# edison_board.net
KiCad netlist of a schematic drawn in EAGLE
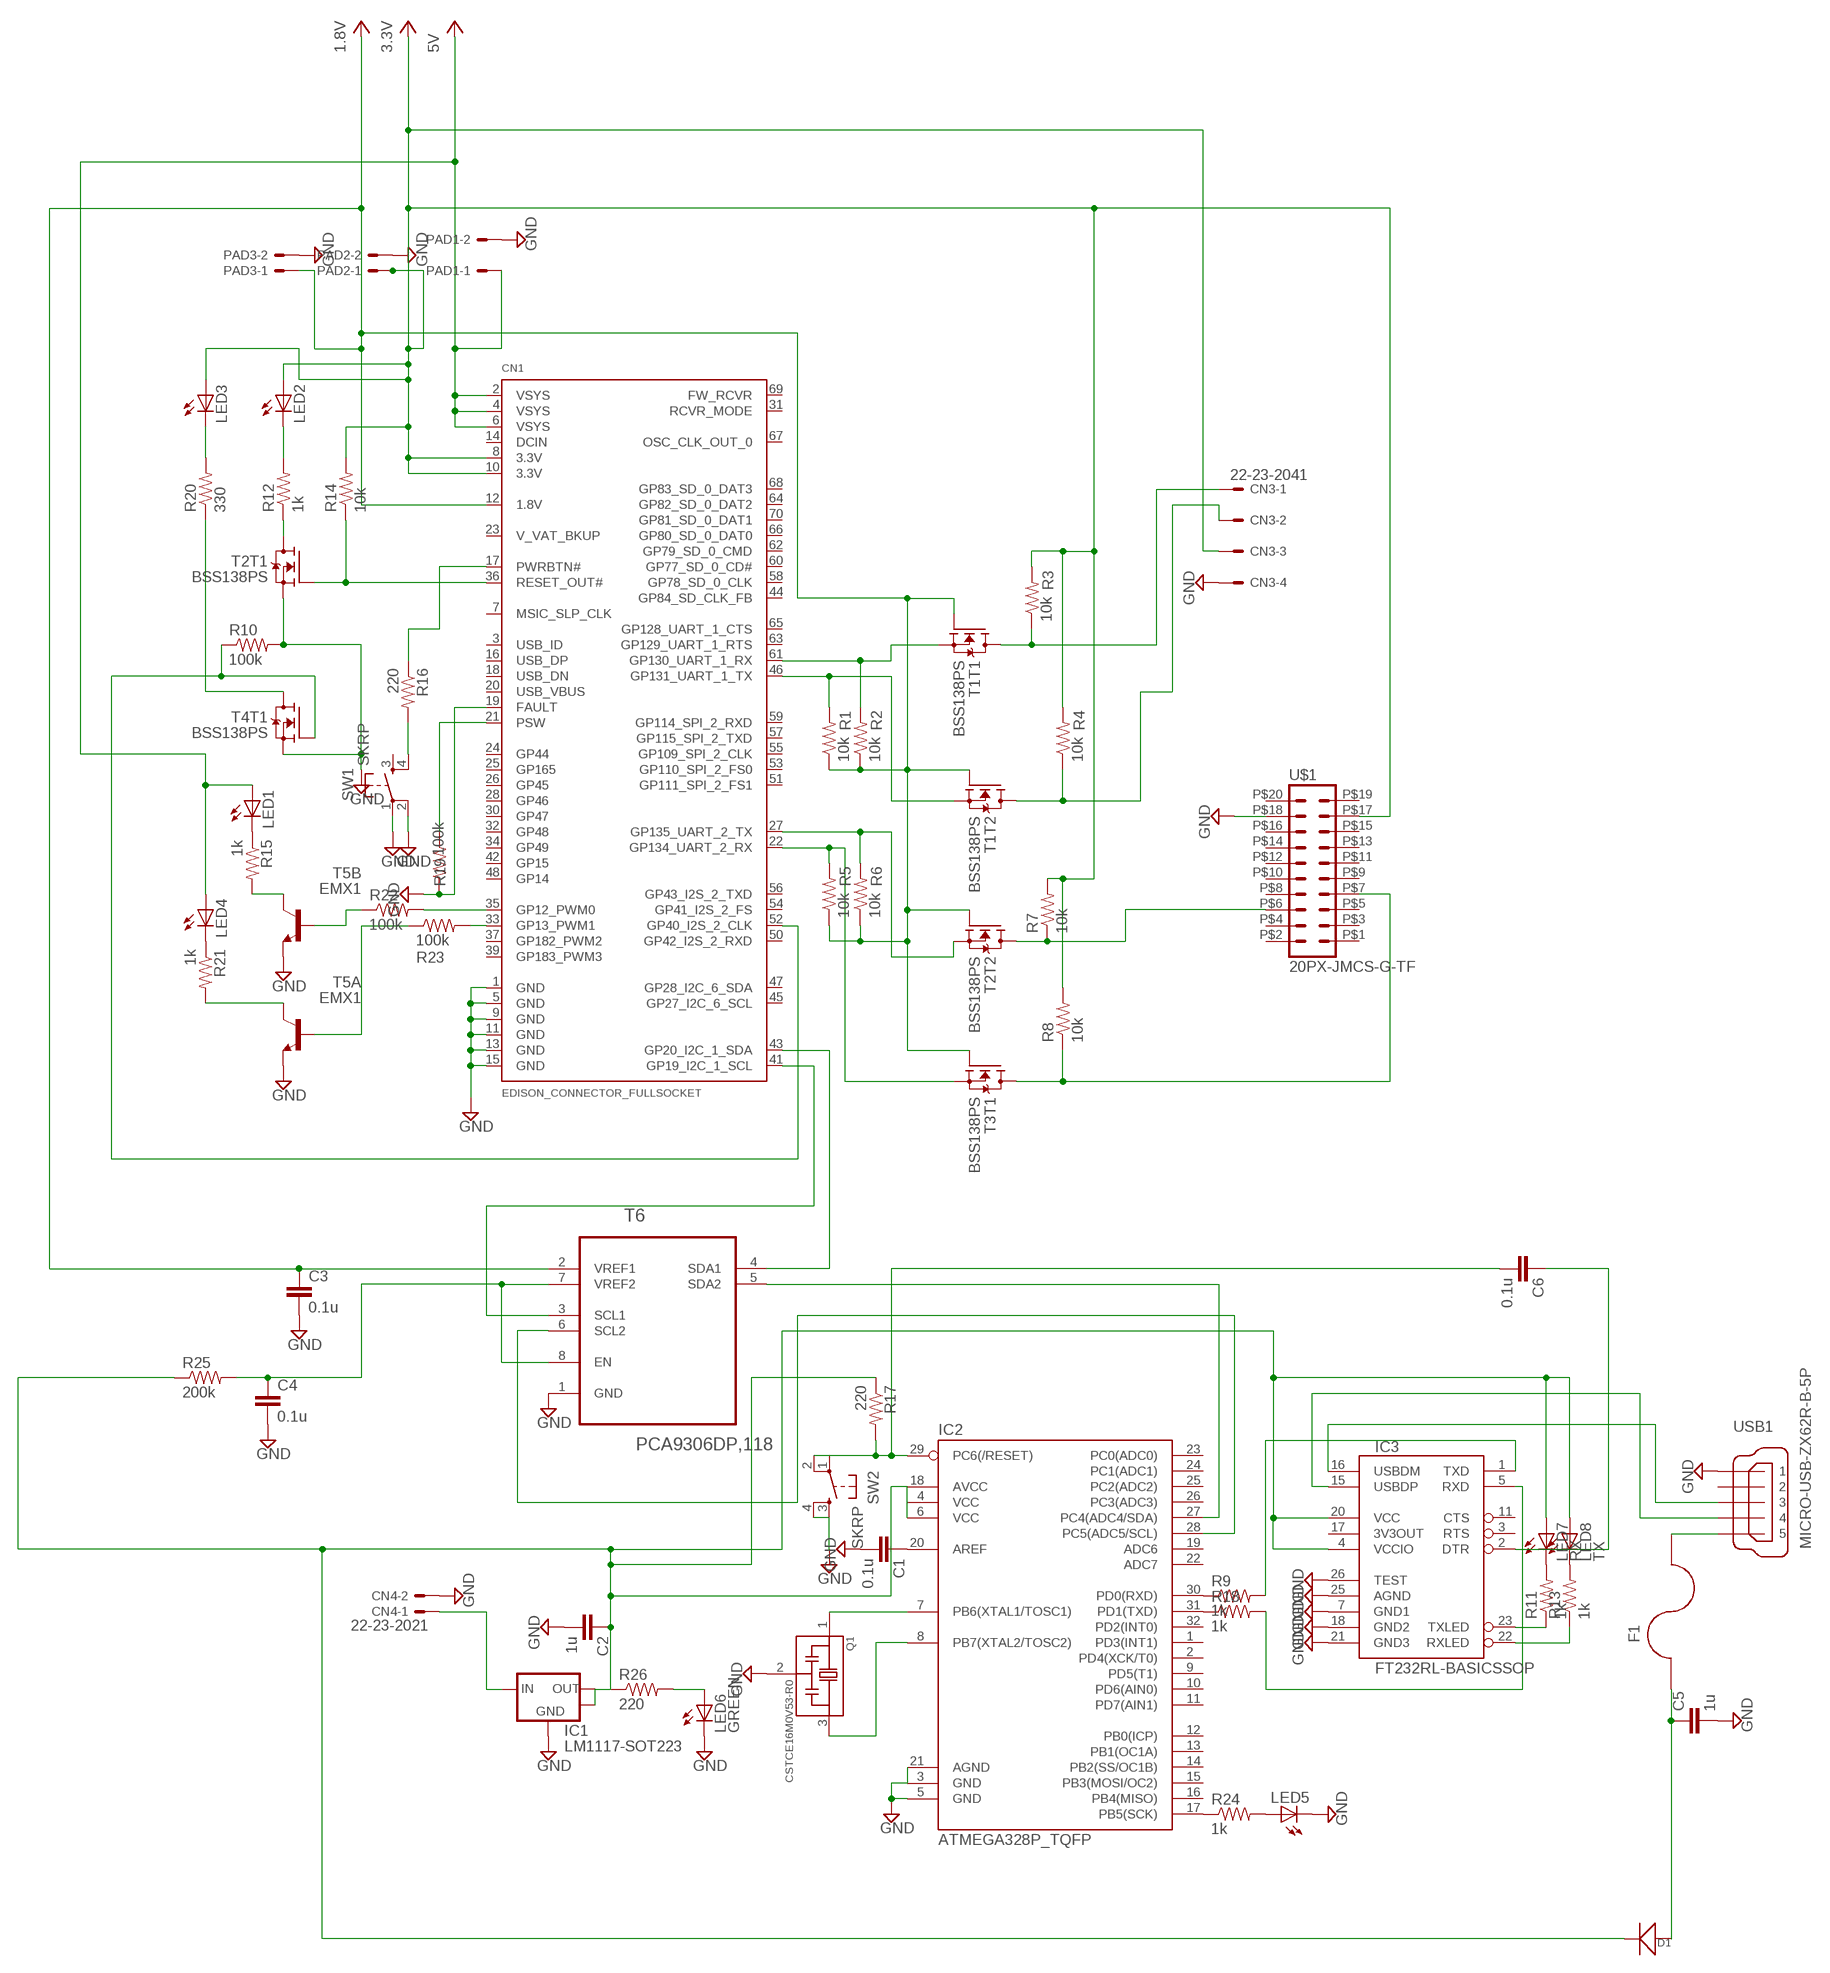
[diagram p0: schematic, sheet 1]

(export (version "E")
  (design (tool "Eeschema 10.0.6"))
  (components
    (comp (ref "C1")
      (value "0.1u")
      (footprint "eagle-import:C0603")
      (libsource (lib "eagle-import") (part "C-EUC0603"))
    )
    (comp (ref "C2")
      (value "1u")
      (footprint "eagle-import:C0603")
      (libsource (lib "eagle-import") (part "C-EUC0603"))
    )
    (comp (ref "C3")
      (value "0.1u")
      (footprint "eagle-import:C0603")
      (libsource (lib "eagle-import") (part "C-EUC0603"))
    )
    (comp (ref "C4")
      (value "0.1u")
      (footprint "eagle-import:C0603")
      (libsource (lib "eagle-import") (part "C-EUC0603"))
    )
    (comp (ref "C5")
      (value "1u")
      (footprint "eagle-import:C0603")
      (libsource (lib "eagle-import") (part "C-EUC0603"))
    )
    (comp (ref "C6")
      (value "0.1u")
      (footprint "eagle-import:C0603")
      (libsource (lib "eagle-import") (part "C-EUC0603"))
    )
    (comp (ref "CN1")
      (value "EDISON_CONNECTOR_FULLSOCKET")
      (footprint "eagle-import:DF40-XC-(X.X)-70DS-0.4V(51)")
      (libsource (lib "eagle-import") (part "EDISON_CONNECTOR_FULLSOCKET"))
    )
    (comp (ref "CN3")
      (value "22-23-2041")
      (footprint "eagle-import:22-23-2041")
      (fields (field (name "MF") "MOLEX"))
      (libsource (lib "eagle-import") (part "22-23-2041"))
    )
    (comp (ref "CN4")
      (value "22-23-2021")
      (footprint "eagle-import:22-23-2021")
      (fields (field (name "MF") "MOLEX"))
      (libsource (lib "eagle-import") (part "22-23-2021"))
    )
    (comp (ref "D1")
      (value "D'DO-220AA'")
      (footprint "eagle-import:DO-220AA")
      (libsource (lib "eagle-import") (part "D'DO-220AA'"))
    )
    (comp (ref "F1")
      (value "MF-MSMF075/24")
      (footprint "eagle-import:1812")
      (fields (field (name "MANUFACTURER") "Bourns Inc.") (field (name "PART_NUMBER") "MF-MSMF075/24-2"))
      (libsource (lib "eagle-import") (part "MF-MSMF?075/24"))
    )
    (comp (ref "IC1")
      (value "LM1117-SOT223")
      (footprint "eagle-import:SOT-223-3")
      (libsource (lib "eagle-import") (part "LM1117-SOT223"))
    )
    (comp (ref "IC2")
      (value "ATMEGA328P_TQFP")
      (footprint "eagle-import:TQFP32-08")
      (libsource (lib "eagle-import") (part "ATMEGA328P_TQFP"))
    )
    (comp (ref "IC3")
      (value "FT232RL-BASICSSOP")
      (footprint "eagle-import:SSOP28DB")
      (libsource (lib "eagle-import") (part "FT232RL-BASICSSOP"))
    )
    (comp (ref "LED1")
      (value "LEDCHIPLED_1206")
      (footprint "eagle-import:CHIPLED_1206")
      (libsource (lib "eagle-import") (part "LEDCHIPLED_1206"))
    )
    (comp (ref "LED2")
      (value "LEDCHIPLED_1206")
      (footprint "eagle-import:CHIPLED_1206")
      (libsource (lib "eagle-import") (part "LEDCHIPLED_1206"))
    )
    (comp (ref "LED3")
      (value "LEDCHIPLED_1206")
      (footprint "eagle-import:CHIPLED_1206")
      (libsource (lib "eagle-import") (part "LEDCHIPLED_1206"))
    )
    (comp (ref "LED4")
      (value "LEDCHIPLED_1206")
      (footprint "eagle-import:CHIPLED_1206")
      (libsource (lib "eagle-import") (part "LEDCHIPLED_1206"))
    )
    (comp (ref "LED5")
      (value "LEDCHIPLED_1206")
      (footprint "eagle-import:CHIPLED_1206")
      (libsource (lib "eagle-import") (part "LEDCHIPLED_1206"))
    )
    (comp (ref "LED6")
      (value "GREEN")
      (footprint "eagle-import:CHIPLED_1206")
      (libsource (lib "eagle-import") (part "LEDCHIPLED_1206"))
    )
    (comp (ref "LED7")
      (value "RX")
      (footprint "eagle-import:CHIPLED_1206")
      (libsource (lib "eagle-import") (part "LEDCHIPLED_1206"))
    )
    (comp (ref "LED8")
      (value "TX")
      (footprint "eagle-import:CHIPLED_1206")
      (libsource (lib "eagle-import") (part "LEDCHIPLED_1206"))
    )
    (comp (ref "PAD1")
      (value "87758-0216")
      (footprint "eagle-import:87758-0216")
      (libsource (lib "eagle-import") (part "87758-0216"))
    )
    (comp (ref "PAD2")
      (value "87758-0216")
      (footprint "eagle-import:87758-0216")
      (libsource (lib "eagle-import") (part "87758-0216"))
    )
    (comp (ref "PAD3")
      (value "87758-0216")
      (footprint "eagle-import:87758-0216")
      (libsource (lib "eagle-import") (part "87758-0216"))
    )
    (comp (ref "Q1")
      (value "CSTCE16M0V53-R0")
      (footprint "eagle-import:OSC_CSTCE16M0V53-R0")
      (fields (field (name "MF") "Murata"))
      (libsource (lib "eagle-import") (part "CSTCE16M0V53-R0"))
    )
    (comp (ref "R1")
      (value "10k")
      (footprint "eagle-import:R0603")
      (libsource (lib "eagle-import") (part "R-US_R0603"))
    )
    (comp (ref "R2")
      (value "10k")
      (footprint "eagle-import:R0603")
      (libsource (lib "eagle-import") (part "R-US_R0603"))
    )
    (comp (ref "R3")
      (value "10k")
      (footprint "eagle-import:R0603")
      (libsource (lib "eagle-import") (part "R-US_R0603"))
    )
    (comp (ref "R4")
      (value "10k")
      (footprint "eagle-import:R0603")
      (libsource (lib "eagle-import") (part "R-US_R0603"))
    )
    (comp (ref "R5")
      (value "10k")
      (footprint "eagle-import:R0603")
      (libsource (lib "eagle-import") (part "R-US_R0603"))
    )
    (comp (ref "R6")
      (value "10k")
      (footprint "eagle-import:R0603")
      (libsource (lib "eagle-import") (part "R-US_R0603"))
    )
    (comp (ref "R7")
      (value "10k")
      (footprint "eagle-import:R0603")
      (libsource (lib "eagle-import") (part "R-US_R0603"))
    )
    (comp (ref "R8")
      (value "10k")
      (footprint "eagle-import:R0603")
      (libsource (lib "eagle-import") (part "R-US_R0603"))
    )
    (comp (ref "R9")
      (value "1k")
      (footprint "eagle-import:R0603")
      (libsource (lib "eagle-import") (part "R-US_R0603"))
    )
    (comp (ref "R10")
      (value "100k")
      (footprint "eagle-import:R0603")
      (libsource (lib "eagle-import") (part "R-US_R0603"))
    )
    (comp (ref "R11")
      (value "1k")
      (footprint "eagle-import:R0603")
      (libsource (lib "eagle-import") (part "R-US_R0603"))
    )
    (comp (ref "R12")
      (value "1k")
      (footprint "eagle-import:R0603")
      (libsource (lib "eagle-import") (part "R-US_R0603"))
    )
    (comp (ref "R13")
      (value "1k")
      (footprint "eagle-import:R0603")
      (libsource (lib "eagle-import") (part "R-US_R0603"))
    )
    (comp (ref "R14")
      (value "10k")
      (footprint "eagle-import:R0603")
      (libsource (lib "eagle-import") (part "R-US_R0603"))
    )
    (comp (ref "R15")
      (value "1k")
      (footprint "eagle-import:R0603")
      (libsource (lib "eagle-import") (part "R-US_R0603"))
    )
    (comp (ref "R16")
      (value "220")
      (footprint "eagle-import:R0603")
      (libsource (lib "eagle-import") (part "R-US_R0603"))
    )
    (comp (ref "R17")
      (value "220")
      (footprint "eagle-import:R0603")
      (libsource (lib "eagle-import") (part "R-US_R0603"))
    )
    (comp (ref "R18")
      (value "1k")
      (footprint "eagle-import:R0603")
      (libsource (lib "eagle-import") (part "R-US_R0603"))
    )
    (comp (ref "R19")
      (value "100k")
      (footprint "eagle-import:R0603")
      (libsource (lib "eagle-import") (part "R-US_R0603"))
    )
    (comp (ref "R20")
      (value "330")
      (footprint "eagle-import:R0603")
      (libsource (lib "eagle-import") (part "R-US_R0603"))
    )
    (comp (ref "R21")
      (value "1k")
      (footprint "eagle-import:R0603")
      (libsource (lib "eagle-import") (part "R-US_R0603"))
    )
    (comp (ref "R22")
      (value "100k")
      (footprint "eagle-import:R0603")
      (libsource (lib "eagle-import") (part "R-US_R0603"))
    )
    (comp (ref "R23")
      (value "100k")
      (footprint "eagle-import:R0603")
      (libsource (lib "eagle-import") (part "R-US_R0603"))
    )
    (comp (ref "R24")
      (value "1k")
      (footprint "eagle-import:R0603")
      (libsource (lib "eagle-import") (part "R-US_R0603"))
    )
    (comp (ref "R25")
      (value "200k")
      (footprint "eagle-import:R0603")
      (libsource (lib "eagle-import") (part "R-US_R0603"))
    )
    (comp (ref "R26")
      (value "220")
      (footprint "eagle-import:R0603")
      (libsource (lib "eagle-import") (part "R-US_R0603"))
    )
    (comp (ref "SW1")
      (value "SKRP")
      (footprint "eagle-import:SKRP")
      (libsource (lib "eagle-import") (part "SKRP"))
    )
    (comp (ref "SW2")
      (value "SKRP")
      (footprint "eagle-import:SKRP")
      (libsource (lib "eagle-import") (part "SKRP"))
    )
    (comp (ref "T1")
      (value "BSS138PS")
      (footprint "eagle-import:SOT363")
      (libsource (lib "eagle-import") (part "BSS138PS"))
    )
    (comp (ref "T2")
      (value "BSS138PS")
      (footprint "eagle-import:SOT363")
      (libsource (lib "eagle-import") (part "BSS138PS"))
    )
    (comp (ref "T3")
      (value "BSS138PS")
      (footprint "eagle-import:SOT363")
      (libsource (lib "eagle-import") (part "BSS138PS"))
    )
    (comp (ref "T4")
      (value "BSS138PS")
      (footprint "eagle-import:SOT363")
      (libsource (lib "eagle-import") (part "BSS138PS"))
    )
    (comp (ref "T5")
      (value "EMX1")
      (footprint "eagle-import:EMT6")
      (fields (field (name "MPN") "EMX1T2R"))
      (libsource (lib "eagle-import") (part "EMX1"))
    )
    (comp (ref "T6")
      (value "PCA9306DP,118")
      (footprint "eagle-import:SOP65P490X110-8N")
      (libsource (lib "eagle-import") (part "PCA9306DP,118"))
    )
    (comp (ref "U$1")
      (value "20PX-JMCS-G-TF")
      (footprint "eagle-import:20PX-JMCS-G-TF")
      (libsource (lib "eagle-import") (part "20PX-JMCS-G-TF"))
    )
    (comp (ref "USB1")
      (value "MICRO-USB-ZX62R-B-5P")
      (footprint "eagle-import:ZX62R-B-5P")
      (libsource (lib "eagle-import") (part "MICRO-USB-ZX62R-B-5P"))
    )
  )
  (nets
    (net (code "1") (name "1.8V") (class "Default")
      (node (ref "C3") (pin "1") (pinfunction "1_1") (pintype "passive"))
      (node (ref "CN1") (pin "12") (pinfunction "1.8V_12") (pintype "bidirectional"))
      (node (ref "CN1") (pin "27") (pinfunction "GP135_UART_2_TX_27") (pintype "bidirectional"))
      (node (ref "PAD3") (pin "1") (pinfunction "S_1") (pintype "passive"))
      (node (ref "R1") (pin "1") (pinfunction "1_1") (pintype "passive"))
      (node (ref "R2") (pin "1") (pinfunction "1_1") (pintype "passive"))
      (node (ref "R5") (pin "1") (pinfunction "1_1") (pintype "passive"))
      (node (ref "R6") (pin "1") (pinfunction "1_1") (pintype "passive"))
      (node (ref "R6") (pin "2") (pinfunction "2_2") (pintype "passive"))
      (node (ref "T1") (pin "2") (pinfunction "G_2") (pintype "passive"))
      (node (ref "T1") (pin "5") (pinfunction "G_5") (pintype "passive"))
      (node (ref "T2") (pin "4") (pinfunction "S_4") (pintype "passive"))
      (node (ref "T2") (pin "5") (pinfunction "G_5") (pintype "passive"))
      (node (ref "T3") (pin "2") (pinfunction "G_2") (pintype "passive"))
      (node (ref "T6") (pin "2") (pinfunction "VREF1_2") (pintype "power_in"))
    )
    (net (code "2") (name "3.3V") (class "Default")
      (node (ref "CN1") (pin "10") (pinfunction "3.3V_10") (pintype "bidirectional"))
      (node (ref "CN1") (pin "8") (pinfunction "3.3V_8") (pintype "bidirectional"))
      (node (ref "CN3") (pin "3") (pinfunction "S_3") (pintype "passive"))
      (node (ref "LED2") (pin "A") (pinfunction "A_A") (pintype "passive"))
      (node (ref "LED3") (pin "A") (pinfunction "A_A") (pintype "passive"))
      (node (ref "PAD2") (pin "1") (pinfunction "S_1") (pintype "passive"))
      (node (ref "R14") (pin "2") (pinfunction "2_2") (pintype "passive"))
      (node (ref "R3") (pin "2") (pinfunction "2_2") (pintype "passive"))
      (node (ref "R4") (pin "2") (pinfunction "2_2") (pintype "passive"))
      (node (ref "R7") (pin "2") (pinfunction "2_2") (pintype "passive"))
      (node (ref "R8") (pin "2") (pinfunction "2_2") (pintype "passive"))
      (node (ref "U$1") (pin "P$17") (pinfunction "17_P$17") (pintype "passive"))
    )
    (net (code "3") (name "5V") (class "Default")
      (node (ref "CN1") (pin "2") (pinfunction "VSYS_2") (pintype "bidirectional"))
      (node (ref "CN1") (pin "4") (pinfunction "VSYS_4") (pintype "bidirectional"))
      (node (ref "CN1") (pin "6") (pinfunction "VSYS_6") (pintype "bidirectional"))
      (node (ref "LED1") (pin "A") (pinfunction "A_A") (pintype "passive"))
      (node (ref "LED4") (pin "A") (pinfunction "A_A") (pintype "passive"))
      (node (ref "PAD1") (pin "1") (pinfunction "S_1") (pintype "passive"))
    )
    (net (code "4") (name "GND") (class "Default")
      (node (ref "C1") (pin "2") (pinfunction "2_2") (pintype "passive"))
      (node (ref "C2") (pin "2") (pinfunction "2_2") (pintype "passive"))
      (node (ref "C3") (pin "2") (pinfunction "2_2") (pintype "passive"))
      (node (ref "C4") (pin "2") (pinfunction "2_2") (pintype "passive"))
      (node (ref "C5") (pin "2") (pinfunction "2_2") (pintype "passive"))
      (node (ref "CN1") (pin "1") (pinfunction "GND_1") (pintype "bidirectional"))
      (node (ref "CN1") (pin "11") (pinfunction "GND_11") (pintype "bidirectional"))
      (node (ref "CN1") (pin "13") (pinfunction "GND_13") (pintype "bidirectional"))
      (node (ref "CN1") (pin "15") (pinfunction "GND_15") (pintype "bidirectional"))
      (node (ref "CN1") (pin "19") (pinfunction "FAULT_19") (pintype "bidirectional"))
      (node (ref "CN1") (pin "5") (pinfunction "GND_5") (pintype "bidirectional"))
      (node (ref "CN1") (pin "9") (pinfunction "GND_9") (pintype "bidirectional"))
      (node (ref "CN3") (pin "4") (pinfunction "S_4") (pintype "passive"))
      (node (ref "CN4") (pin "2") (pinfunction "S_2") (pintype "passive"))
      (node (ref "IC1") (pin "1") (pinfunction "GND_1") (pintype "bidirectional"))
      (node (ref "IC2") (pin "21") (pinfunction "AGND_21") (pintype "bidirectional"))
      (node (ref "IC2") (pin "3") (pinfunction "GND_3") (pintype "bidirectional"))
      (node (ref "IC2") (pin "5") (pinfunction "GND_5") (pintype "bidirectional"))
      (node (ref "IC3") (pin "18") (pinfunction "GND2_18") (pintype "power_in"))
      (node (ref "IC3") (pin "21") (pinfunction "GND3_21") (pintype "power_in"))
      (node (ref "IC3") (pin "25") (pinfunction "AGND_25") (pintype "power_in"))
      (node (ref "IC3") (pin "26") (pinfunction "TEST_26") (pintype "input"))
      (node (ref "IC3") (pin "7") (pinfunction "GND1_7") (pintype "power_in"))
      (node (ref "LED5") (pin "C") (pinfunction "C_C") (pintype "passive"))
      (node (ref "LED6") (pin "C") (pinfunction "C_C") (pintype "passive"))
      (node (ref "PAD1") (pin "2") (pinfunction "S_2") (pintype "passive"))
      (node (ref "PAD2") (pin "2") (pinfunction "S_2") (pintype "passive"))
      (node (ref "PAD3") (pin "2") (pinfunction "S_2") (pintype "passive"))
      (node (ref "Q1") (pin "2") (pinfunction "2_2") (pintype "power_in"))
      (node (ref "R10") (pin "2") (pinfunction "2_2") (pintype "passive"))
      (node (ref "R19") (pin "1") (pinfunction "1_1") (pintype "passive"))
      (node (ref "SW1") (pin "1") (pinfunction "1_1") (pintype "passive"))
      (node (ref "SW1") (pin "2") (pinfunction "2_2") (pintype "passive"))
      (node (ref "SW2") (pin "3") (pinfunction "3_3") (pintype "passive"))
      (node (ref "SW2") (pin "4") (pinfunction "4_4") (pintype "passive"))
      (node (ref "T2") (pin "1") (pinfunction "S_1") (pintype "passive"))
      (node (ref "T4") (pin "1") (pinfunction "S_1") (pintype "passive"))
      (node (ref "T5") (pin "1") (pinfunction "E_1") (pintype "passive"))
      (node (ref "T5") (pin "4") (pinfunction "E_4") (pintype "passive"))
      (node (ref "T6") (pin "1") (pinfunction "GND_1") (pintype "passive"))
      (node (ref "U$1") (pin "P$18") (pinfunction "18_P$18") (pintype "passive"))
      (node (ref "USB1") (pin "1") (pinfunction "1_1") (pintype "input"))
    )
    (net (code "5") (name "Net-(C5-Pad1)") (class "Default")
      (node (ref "C5") (pin "1") (pinfunction "1_1") (pintype "passive"))
      (node (ref "D1") (pin "+") (pinfunction "+_+") (pintype "passive"))
      (node (ref "F1") (pin "2") (pinfunction "2_2") (pintype "passive"))
    )
    (net (code "6") (name "Net-(CN1-GP12_PWM0)") (class "Default")
      (node (ref "CN1") (pin "35") (pinfunction "GP12_PWM0_35") (pintype "bidirectional"))
      (node (ref "R22") (pin "2") (pinfunction "2_2") (pintype "passive"))
    )
    (net (code "7") (name "Net-(CN1-GP13_PWM1)") (class "Default")
      (node (ref "CN1") (pin "33") (pinfunction "GP13_PWM1_33") (pintype "bidirectional"))
      (node (ref "R23") (pin "2") (pinfunction "2_2") (pintype "passive"))
    )
    (net (code "8") (name "Net-(CN1-GP19_I2C_1_SCL)") (class "Default")
      (node (ref "CN1") (pin "41") (pinfunction "GP19_I2C_1_SCL_41") (pintype "bidirectional"))
      (node (ref "T6") (pin "3") (pinfunction "SCL1_3") (pintype "input"))
    )
    (net (code "9") (name "Net-(CN1-GP20_I2C_1_SDA)") (class "Default")
      (node (ref "CN1") (pin "43") (pinfunction "GP20_I2C_1_SDA_43") (pintype "bidirectional"))
      (node (ref "T6") (pin "4") (pinfunction "SDA1_4") (pintype "bidirectional"))
    )
    (net (code "10") (name "Net-(CN1-GP40_I2S_2_CLK)") (class "Default")
      (node (ref "CN1") (pin "52") (pinfunction "GP40_I2S_2_CLK_52") (pintype "bidirectional"))
      (node (ref "R10") (pin "1") (pinfunction "1_1") (pintype "passive"))
      (node (ref "T4") (pin "2") (pinfunction "G_2") (pintype "passive"))
    )
    (net (code "11") (name "Net-(CN1-GP130_UART_1_RX)") (class "Default")
      (node (ref "CN1") (pin "61") (pinfunction "GP130_UART_1_RX_61") (pintype "bidirectional"))
      (node (ref "R2") (pin "2") (pinfunction "2_2") (pintype "passive"))
      (node (ref "T1") (pin "1") (pinfunction "S_1") (pintype "passive"))
    )
    (net (code "12") (name "Net-(CN1-GP131_UART_1_TX)") (class "Default")
      (node (ref "CN1") (pin "46") (pinfunction "GP131_UART_1_TX_46") (pintype "bidirectional"))
      (node (ref "R1") (pin "2") (pinfunction "2_2") (pintype "passive"))
      (node (ref "T1") (pin "4") (pinfunction "S_4") (pintype "passive"))
    )
    (net (code "13") (name "Net-(CN1-GP134_UART_2_RX)") (class "Default")
      (node (ref "CN1") (pin "22") (pinfunction "GP134_UART_2_RX_22") (pintype "bidirectional"))
      (node (ref "R5") (pin "2") (pinfunction "2_2") (pintype "passive"))
      (node (ref "T3") (pin "1") (pinfunction "S_1") (pintype "passive"))
    )
    (net (code "14") (name "Net-(CN1-PSW)") (class "Default")
      (node (ref "CN1") (pin "21") (pinfunction "PSW_21") (pintype "bidirectional"))
      (node (ref "R19") (pin "2") (pinfunction "2_2") (pintype "passive"))
    )
    (net (code "15") (name "Net-(CN1-PWRBTN#)") (class "Default")
      (node (ref "CN1") (pin "17") (pinfunction "PWRBTN#_17") (pintype "bidirectional"))
      (node (ref "R16") (pin "1") (pinfunction "1_1") (pintype "passive"))
    )
    (net (code "16") (name "Net-(CN1-RESET_OUT#)") (class "Default")
      (node (ref "CN1") (pin "36") (pinfunction "RESET_OUT#_36") (pintype "bidirectional"))
      (node (ref "R14") (pin "1") (pinfunction "1_1") (pintype "passive"))
      (node (ref "T2") (pin "2") (pinfunction "G_2") (pintype "passive"))
    )
    (net (code "17") (name "Net-(CN3A-S)") (class "Default")
      (node (ref "CN3") (pin "1") (pinfunction "S_1") (pintype "passive"))
      (node (ref "R3") (pin "1") (pinfunction "1_1") (pintype "passive"))
      (node (ref "T1") (pin "6") (pinfunction "D_6") (pintype "passive"))
    )
    (net (code "18") (name "Net-(CN3B-S)") (class "Default")
      (node (ref "CN3") (pin "2") (pinfunction "S_2") (pintype "passive"))
      (node (ref "R4") (pin "1") (pinfunction "1_1") (pintype "passive"))
      (node (ref "T1") (pin "3") (pinfunction "D_3") (pintype "passive"))
    )
    (net (code "19") (name "Net-(CN4A-S)") (class "Default")
      (node (ref "CN4") (pin "1") (pinfunction "S_1") (pintype "passive"))
      (node (ref "IC1") (pin "3") (pinfunction "VIN_3") (pintype "bidirectional"))
    )
    (net (code "20") (name "Net-(F1-Pad1)") (class "Default")
      (node (ref "F1") (pin "1") (pinfunction "1_1") (pintype "passive"))
      (node (ref "USB1") (pin "5") (pinfunction "5_5") (pintype "input"))
    )
    (net (code "21") (name "Net-(IC1-HEATSINK)") (class "Default")
      (node (ref "C2") (pin "1") (pinfunction "1_1") (pintype "passive"))
      (node (ref "D1") (pin "-") (pinfunction "-_-") (pintype "passive"))
      (node (ref "IC1") (pin "2") (pinfunction "VOUT_2") (pintype "bidirectional"))
      (node (ref "IC1") (pin "4") (pinfunction "HEATSINK_4") (pintype "bidirectional"))
      (node (ref "IC2") (pin "18") (pinfunction "AVCC_18") (pintype "bidirectional"))
      (node (ref "IC2") (pin "4") (pinfunction "VCC_4") (pintype "bidirectional"))
      (node (ref "IC2") (pin "6") (pinfunction "VCC_6") (pintype "bidirectional"))
      (node (ref "IC3") (pin "20") (pinfunction "VCC_20") (pintype "power_in"))
      (node (ref "IC3") (pin "4") (pinfunction "VCCIO_4") (pintype "power_in"))
      (node (ref "LED7") (pin "A") (pinfunction "A_A") (pintype "passive"))
      (node (ref "LED8") (pin "A") (pinfunction "A_A") (pintype "passive"))
      (node (ref "R17") (pin "1") (pinfunction "1_1") (pintype "passive"))
      (node (ref "R25") (pin "1") (pinfunction "1_1") (pintype "passive"))
      (node (ref "R26") (pin "1") (pinfunction "1_1") (pintype "passive"))
    )
    (net (code "22") (name "Net-(IC2-AREF)") (class "Default")
      (node (ref "C1") (pin "1") (pinfunction "1_1") (pintype "passive"))
      (node (ref "IC2") (pin "20") (pinfunction "AREF_20") (pintype "bidirectional"))
    )
    (net (code "23") (name "Net-(IC2-PB5(SCK))") (class "Default")
      (node (ref "IC2") (pin "17") (pinfunction "PB5(SCK)_17") (pintype "bidirectional"))
      (node (ref "R24") (pin "1") (pinfunction "1_1") (pintype "passive"))
    )
    (net (code "24") (name "Net-(IC2-PB6(XTAL1{slash}TOSC1))") (class "Default")
      (node (ref "IC2") (pin "7") (pinfunction "PB6(XTAL1/TOSC1)_7") (pintype "bidirectional"))
      (node (ref "Q1") (pin "1") (pinfunction "1_1") (pintype "passive"))
    )
    (net (code "25") (name "Net-(IC2-PB7(XTAL2{slash}TOSC2))") (class "Default")
      (node (ref "IC2") (pin "8") (pinfunction "PB7(XTAL2/TOSC2)_8") (pintype "bidirectional"))
      (node (ref "Q1") (pin "3") (pinfunction "3_3") (pintype "passive"))
    )
    (net (code "26") (name "Net-(IC2-PC4(ADC4{slash}SDA))") (class "Default")
      (node (ref "IC2") (pin "27") (pinfunction "PC4(ADC4/SDA)_27") (pintype "bidirectional"))
      (node (ref "T6") (pin "5") (pinfunction "SDA2_5") (pintype "bidirectional"))
    )
    (net (code "27") (name "Net-(IC2-PC5(ADC5{slash}SCL))") (class "Default")
      (node (ref "IC2") (pin "28") (pinfunction "PC5(ADC5/SCL)_28") (pintype "bidirectional"))
      (node (ref "T6") (pin "6") (pinfunction "SCL2_6") (pintype "input"))
    )
    (net (code "28") (name "Net-(IC2-PC6({slash}RESET))") (class "Default")
      (node (ref "C6") (pin "2") (pinfunction "2_2") (pintype "passive"))
      (node (ref "IC2") (pin "29") (pinfunction "PC6(/RESET)_29") (pintype "bidirectional"))
      (node (ref "R17") (pin "2") (pinfunction "2_2") (pintype "passive"))
      (node (ref "SW2") (pin "1") (pinfunction "1_1") (pintype "passive"))
      (node (ref "SW2") (pin "2") (pinfunction "2_2") (pintype "passive"))
    )
    (net (code "29") (name "Net-(IC2-PD0(RXD))") (class "Default")
      (node (ref "IC2") (pin "30") (pinfunction "PD0(RXD)_30") (pintype "bidirectional"))
      (node (ref "R9") (pin "1") (pinfunction "1_1") (pintype "passive"))
    )
    (net (code "30") (name "Net-(IC2-PD1(TXD))") (class "Default")
      (node (ref "IC2") (pin "31") (pinfunction "PD1(TXD)_31") (pintype "bidirectional"))
      (node (ref "R18") (pin "1") (pinfunction "1_1") (pintype "passive"))
    )
    (net (code "31") (name "Net-(IC3-DTR)") (class "Default")
      (node (ref "C6") (pin "1") (pinfunction "1_1") (pintype "passive"))
      (node (ref "IC3") (pin "2") (pinfunction "DTR_2") (pintype "bidirectional"))
    )
    (net (code "32") (name "Net-(IC3-RXD)") (class "Default")
      (node (ref "IC3") (pin "5") (pinfunction "RXD_5") (pintype "input"))
      (node (ref "R18") (pin "2") (pinfunction "2_2") (pintype "passive"))
    )
    (net (code "33") (name "Net-(IC3-RXLED)") (class "Default")
      (node (ref "IC3") (pin "22") (pinfunction "RXLED_22") (pintype "bidirectional"))
      (node (ref "R13") (pin "1") (pinfunction "1_1") (pintype "passive"))
    )
    (net (code "34") (name "Net-(IC3-TXD)") (class "Default")
      (node (ref "IC3") (pin "1") (pinfunction "TXD_1") (pintype "output"))
      (node (ref "R9") (pin "2") (pinfunction "2_2") (pintype "passive"))
    )
    (net (code "35") (name "Net-(IC3-TXLED)") (class "Default")
      (node (ref "IC3") (pin "23") (pinfunction "TXLED_23") (pintype "bidirectional"))
      (node (ref "R11") (pin "1") (pinfunction "1_1") (pintype "passive"))
    )
    (net (code "36") (name "Net-(IC3-USBDM)") (class "Default")
      (node (ref "IC3") (pin "16") (pinfunction "USBDM_16") (pintype "bidirectional"))
      (node (ref "USB1") (pin "3") (pinfunction "3_3") (pintype "input"))
    )
    (net (code "37") (name "Net-(IC3-USBDP)") (class "Default")
      (node (ref "IC3") (pin "15") (pinfunction "USBDP_15") (pintype "bidirectional"))
      (node (ref "USB1") (pin "4") (pinfunction "4_4") (pintype "input"))
    )
    (net (code "38") (name "Net-(LED1-PadC)") (class "Default")
      (node (ref "LED1") (pin "C") (pinfunction "C_C") (pintype "passive"))
      (node (ref "R15") (pin "1") (pinfunction "1_1") (pintype "passive"))
    )
    (net (code "39") (name "Net-(LED2-PadC)") (class "Default")
      (node (ref "LED2") (pin "C") (pinfunction "C_C") (pintype "passive"))
      (node (ref "R12") (pin "2") (pinfunction "2_2") (pintype "passive"))
    )
    (net (code "40") (name "Net-(LED3-PadC)") (class "Default")
      (node (ref "LED3") (pin "C") (pinfunction "C_C") (pintype "passive"))
      (node (ref "R20") (pin "2") (pinfunction "2_2") (pintype "passive"))
    )
    (net (code "41") (name "Net-(LED4-PadC)") (class "Default")
      (node (ref "LED4") (pin "C") (pinfunction "C_C") (pintype "passive"))
      (node (ref "R21") (pin "1") (pinfunction "1_1") (pintype "passive"))
    )
    (net (code "42") (name "Net-(LED5-PadA)") (class "Default")
      (node (ref "LED5") (pin "A") (pinfunction "A_A") (pintype "passive"))
      (node (ref "R24") (pin "2") (pinfunction "2_2") (pintype "passive"))
    )
    (net (code "43") (name "Net-(LED6-PadA)") (class "Default")
      (node (ref "LED6") (pin "A") (pinfunction "A_A") (pintype "passive"))
      (node (ref "R26") (pin "2") (pinfunction "2_2") (pintype "passive"))
    )
    (net (code "44") (name "Net-(LED7-PadC)") (class "Default")
      (node (ref "LED7") (pin "C") (pinfunction "C_C") (pintype "passive"))
      (node (ref "R11") (pin "2") (pinfunction "2_2") (pintype "passive"))
    )
    (net (code "45") (name "Net-(LED8-PadC)") (class "Default")
      (node (ref "LED8") (pin "C") (pinfunction "C_C") (pintype "passive"))
      (node (ref "R13") (pin "2") (pinfunction "2_2") (pintype "passive"))
    )
    (net (code "46") (name "Net-(R16-Pad2)") (class "Default")
      (node (ref "R16") (pin "2") (pinfunction "2_2") (pintype "passive"))
      (node (ref "SW1") (pin "4") (pinfunction "4_4") (pintype "passive"))
    )
    (net (code "47") (name "Net-(T2A-D)") (class "Default")
      (node (ref "R12") (pin "1") (pinfunction "1_1") (pintype "passive"))
      (node (ref "T2") (pin "6") (pinfunction "D_6") (pintype "passive"))
    )
    (net (code "48") (name "Net-(T2B-D)") (class "Default")
      (node (ref "R7") (pin "1") (pinfunction "1_1") (pintype "passive"))
      (node (ref "T2") (pin "3") (pinfunction "D_3") (pintype "passive"))
      (node (ref "U$1") (pin "P$6") (pinfunction "6_P$6") (pintype "passive"))
    )
    (net (code "49") (name "Net-(T3A-D)") (class "Default")
      (node (ref "R8") (pin "1") (pinfunction "1_1") (pintype "passive"))
      (node (ref "T3") (pin "6") (pinfunction "D_6") (pintype "passive"))
      (node (ref "U$1") (pin "P$7") (pinfunction "7_P$7") (pintype "passive"))
    )
    (net (code "50") (name "Net-(T4A-D)") (class "Default")
      (node (ref "R20") (pin "1") (pinfunction "1_1") (pintype "passive"))
      (node (ref "T4") (pin "6") (pinfunction "D_6") (pintype "passive"))
    )
    (net (code "51") (name "Net-(T5A-B)") (class "Default")
      (node (ref "R23") (pin "1") (pinfunction "1_1") (pintype "passive"))
      (node (ref "T5") (pin "2") (pinfunction "B_2") (pintype "passive"))
    )
    (net (code "52") (name "Net-(T5A-C)") (class "Default")
      (node (ref "R21") (pin "2") (pinfunction "2_2") (pintype "passive"))
      (node (ref "T5") (pin "6") (pinfunction "C_6") (pintype "passive"))
    )
    (net (code "53") (name "Net-(T5B-B)") (class "Default")
      (node (ref "R22") (pin "1") (pinfunction "1_1") (pintype "passive"))
      (node (ref "T5") (pin "5") (pinfunction "B_5") (pintype "passive"))
    )
    (net (code "54") (name "Net-(T5B-C)") (class "Default")
      (node (ref "R15") (pin "2") (pinfunction "2_2") (pintype "passive"))
      (node (ref "T5") (pin "3") (pinfunction "C_3") (pintype "passive"))
    )
    (net (code "55") (name "Net-(T6-EN)") (class "Default")
      (node (ref "C4") (pin "1") (pinfunction "1_1") (pintype "passive"))
      (node (ref "R25") (pin "2") (pinfunction "2_2") (pintype "passive"))
      (node (ref "T6") (pin "7") (pinfunction "VREF2_7") (pintype "power_in"))
      (node (ref "T6") (pin "8") (pinfunction "EN_8") (pintype "input"))
    )
    (net (code "56") (name "unconnected-(CN1-DCIN-Pad14)") (class "Default")
      (node (ref "CN1") (pin "14") (pinfunction "DCIN_14") (pintype "bidirectional"))
    )
    (net (code "57") (name "unconnected-(CN1-FW_RCVR-Pad69)") (class "Default")
      (node (ref "CN1") (pin "69") (pinfunction "FW_RCVR_69") (pintype "bidirectional"))
    )
    (net (code "58") (name "unconnected-(CN1-GP14-Pad48)") (class "Default")
      (node (ref "CN1") (pin "48") (pinfunction "GP14_48") (pintype "bidirectional"))
    )
    (net (code "59") (name "unconnected-(CN1-GP15-Pad42)") (class "Default")
      (node (ref "CN1") (pin "42") (pinfunction "GP15_42") (pintype "bidirectional"))
    )
    (net (code "60") (name "unconnected-(CN1-GP27_I2C_6_SCL-Pad45)") (class "Default")
      (node (ref "CN1") (pin "45") (pinfunction "GP27_I2C_6_SCL_45") (pintype "bidirectional"))
    )
    (net (code "61") (name "unconnected-(CN1-GP28_I2C_6_SDA-Pad47)") (class "Default")
      (node (ref "CN1") (pin "47") (pinfunction "GP28_I2C_6_SDA_47") (pintype "bidirectional"))
    )
    (net (code "62") (name "unconnected-(CN1-GP41_I2S_2_FS-Pad54)") (class "Default")
      (node (ref "CN1") (pin "54") (pinfunction "GP41_I2S_2_FS_54") (pintype "bidirectional"))
    )
    (net (code "63") (name "unconnected-(CN1-GP42_I2S_2_RXD-Pad50)") (class "Default")
      (node (ref "CN1") (pin "50") (pinfunction "GP42_I2S_2_RXD_50") (pintype "bidirectional"))
    )
    (net (code "64") (name "unconnected-(CN1-GP43_I2S_2_TXD-Pad56)") (class "Default")
      (node (ref "CN1") (pin "56") (pinfunction "GP43_I2S_2_TXD_56") (pintype "bidirectional"))
    )
    (net (code "65") (name "unconnected-(CN1-GP44-Pad24)") (class "Default")
      (node (ref "CN1") (pin "24") (pinfunction "GP44_24") (pintype "bidirectional"))
    )
    (net (code "66") (name "unconnected-(CN1-GP45-Pad26)") (class "Default")
      (node (ref "CN1") (pin "26") (pinfunction "GP45_26") (pintype "bidirectional"))
    )
    (net (code "67") (name "unconnected-(CN1-GP46-Pad28)") (class "Default")
      (node (ref "CN1") (pin "28") (pinfunction "GP46_28") (pintype "bidirectional"))
    )
    (net (code "68") (name "unconnected-(CN1-GP47-Pad30)") (class "Default")
      (node (ref "CN1") (pin "30") (pinfunction "GP47_30") (pintype "bidirectional"))
    )
    (net (code "69") (name "unconnected-(CN1-GP48-Pad32)") (class "Default")
      (node (ref "CN1") (pin "32") (pinfunction "GP48_32") (pintype "bidirectional"))
    )
    (net (code "70") (name "unconnected-(CN1-GP49-Pad34)") (class "Default")
      (node (ref "CN1") (pin "34") (pinfunction "GP49_34") (pintype "bidirectional"))
    )
    (net (code "71") (name "unconnected-(CN1-GP77_SD_0_CD#-Pad60)") (class "Default")
      (node (ref "CN1") (pin "60") (pinfunction "GP77_SD_0_CD#_60") (pintype "bidirectional"))
    )
    (net (code "72") (name "unconnected-(CN1-GP78_SD_0_CLK-Pad58)") (class "Default")
      (node (ref "CN1") (pin "58") (pinfunction "GP78_SD_0_CLK_58") (pintype "bidirectional"))
    )
    (net (code "73") (name "unconnected-(CN1-GP79_SD_0_CMD-Pad62)") (class "Default")
      (node (ref "CN1") (pin "62") (pinfunction "GP79_SD_0_CMD_62") (pintype "bidirectional"))
    )
    (net (code "74") (name "unconnected-(CN1-GP80_SD_0_DAT0-Pad66)") (class "Default")
      (node (ref "CN1") (pin "66") (pinfunction "GP80_SD_0_DAT0_66") (pintype "bidirectional"))
    )
    (net (code "75") (name "unconnected-(CN1-GP81_SD_0_DAT1-Pad70)") (class "Default")
      (node (ref "CN1") (pin "70") (pinfunction "GP81_SD_0_DAT1_70") (pintype "bidirectional"))
    )
    (net (code "76") (name "unconnected-(CN1-GP82_SD_0_DAT2-Pad64)") (class "Default")
      (node (ref "CN1") (pin "64") (pinfunction "GP82_SD_0_DAT2_64") (pintype "bidirectional"))
    )
    (net (code "77") (name "unconnected-(CN1-GP83_SD_0_DAT3-Pad68)") (class "Default")
      (node (ref "CN1") (pin "68") (pinfunction "GP83_SD_0_DAT3_68") (pintype "bidirectional"))
    )
    (net (code "78") (name "unconnected-(CN1-GP84_SD_CLK_FB-Pad44)") (class "Default")
      (node (ref "CN1") (pin "44") (pinfunction "GP84_SD_CLK_FB_44") (pintype "bidirectional"))
    )
    (net (code "79") (name "unconnected-(CN1-GP109_SPI_2_CLK-Pad55)") (class "Default")
      (node (ref "CN1") (pin "55") (pinfunction "GP109_SPI_2_CLK_55") (pintype "bidirectional"))
    )
    (net (code "80") (name "unconnected-(CN1-GP110_SPI_2_FS0-Pad53)") (class "Default")
      (node (ref "CN1") (pin "53") (pinfunction "GP110_SPI_2_FS0_53") (pintype "bidirectional"))
    )
    (net (code "81") (name "unconnected-(CN1-GP111_SPI_2_FS1-Pad51)") (class "Default")
      (node (ref "CN1") (pin "51") (pinfunction "GP111_SPI_2_FS1_51") (pintype "bidirectional"))
    )
    (net (code "82") (name "unconnected-(CN1-GP114_SPI_2_RXD-Pad59)") (class "Default")
      (node (ref "CN1") (pin "59") (pinfunction "GP114_SPI_2_RXD_59") (pintype "bidirectional"))
    )
    (net (code "83") (name "unconnected-(CN1-GP115_SPI_2_TXD-Pad57)") (class "Default")
      (node (ref "CN1") (pin "57") (pinfunction "GP115_SPI_2_TXD_57") (pintype "bidirectional"))
    )
    (net (code "84") (name "unconnected-(CN1-GP128_UART_1_CTS-Pad65)") (class "Default")
      (node (ref "CN1") (pin "65") (pinfunction "GP128_UART_1_CTS_65") (pintype "bidirectional"))
    )
    (net (code "85") (name "unconnected-(CN1-GP129_UART_1_RTS-Pad63)") (class "Default")
      (node (ref "CN1") (pin "63") (pinfunction "GP129_UART_1_RTS_63") (pintype "bidirectional"))
    )
    (net (code "86") (name "unconnected-(CN1-GP165-Pad25)") (class "Default")
      (node (ref "CN1") (pin "25") (pinfunction "GP165_25") (pintype "bidirectional"))
    )
    (net (code "87") (name "unconnected-(CN1-GP182_PWM2-Pad37)") (class "Default")
      (node (ref "CN1") (pin "37") (pinfunction "GP182_PWM2_37") (pintype "bidirectional"))
    )
    (net (code "88") (name "unconnected-(CN1-GP183_PWM3-Pad39)") (class "Default")
      (node (ref "CN1") (pin "39") (pinfunction "GP183_PWM3_39") (pintype "bidirectional"))
    )
    (net (code "89") (name "unconnected-(CN1-MSIC_SLP_CLK-Pad7)") (class "Default")
      (node (ref "CN1") (pin "7") (pinfunction "MSIC_SLP_CLK_7") (pintype "bidirectional"))
    )
    (net (code "90") (name "unconnected-(CN1-OSC_CLK_OUT_0-Pad67)") (class "Default")
      (node (ref "CN1") (pin "67") (pinfunction "OSC_CLK_OUT_0_67") (pintype "bidirectional"))
    )
    (net (code "91") (name "unconnected-(CN1-RCVR_MODE-Pad31)") (class "Default")
      (node (ref "CN1") (pin "31") (pinfunction "RCVR_MODE_31") (pintype "bidirectional"))
    )
    (net (code "92") (name "unconnected-(CN1-USB_DN-Pad18)") (class "Default")
      (node (ref "CN1") (pin "18") (pinfunction "USB_DN_18") (pintype "bidirectional"))
    )
    (net (code "93") (name "unconnected-(CN1-USB_DP-Pad16)") (class "Default")
      (node (ref "CN1") (pin "16") (pinfunction "USB_DP_16") (pintype "bidirectional"))
    )
    (net (code "94") (name "unconnected-(CN1-USB_ID-Pad3)") (class "Default")
      (node (ref "CN1") (pin "3") (pinfunction "USB_ID_3") (pintype "bidirectional"))
    )
    (net (code "95") (name "unconnected-(CN1-USB_VBUS-Pad20)") (class "Default")
      (node (ref "CN1") (pin "20") (pinfunction "USB_VBUS_20") (pintype "bidirectional"))
    )
    (net (code "96") (name "unconnected-(CN1-V_VAT_BKUP-Pad23)") (class "Default")
      (node (ref "CN1") (pin "23") (pinfunction "V_VAT_BKUP_23") (pintype "bidirectional"))
    )
    (net (code "97") (name "unconnected-(IC2-ADC6-Pad19)") (class "Default")
      (node (ref "IC2") (pin "19") (pinfunction "ADC6_19") (pintype "bidirectional"))
    )
    (net (code "98") (name "unconnected-(IC2-ADC7-Pad22)") (class "Default")
      (node (ref "IC2") (pin "22") (pinfunction "ADC7_22") (pintype "bidirectional"))
    )
    (net (code "99") (name "unconnected-(IC2-PB0(ICP)-Pad12)") (class "Default")
      (node (ref "IC2") (pin "12") (pinfunction "PB0(ICP)_12") (pintype "bidirectional"))
    )
    (net (code "100") (name "unconnected-(IC2-PB1(OC1A)-Pad13)") (class "Default")
      (node (ref "IC2") (pin "13") (pinfunction "PB1(OC1A)_13") (pintype "bidirectional"))
    )
    (net (code "101") (name "unconnected-(IC2-PB2(SS{slash}OC1B)-Pad14)") (class "Default")
      (node (ref "IC2") (pin "14") (pinfunction "PB2(SS/OC1B)_14") (pintype "bidirectional"))
    )
    (net (code "102") (name "unconnected-(IC2-PB3(MOSI{slash}OC2)-Pad15)") (class "Default")
      (node (ref "IC2") (pin "15") (pinfunction "PB3(MOSI/OC2)_15") (pintype "bidirectional"))
    )
    (net (code "103") (name "unconnected-(IC2-PB4(MISO)-Pad16)") (class "Default")
      (node (ref "IC2") (pin "16") (pinfunction "PB4(MISO)_16") (pintype "bidirectional"))
    )
    (net (code "104") (name "unconnected-(IC2-PC0(ADC0)-Pad23)") (class "Default")
      (node (ref "IC2") (pin "23") (pinfunction "PC0(ADC0)_23") (pintype "bidirectional"))
    )
    (net (code "105") (name "unconnected-(IC2-PC1(ADC1)-Pad24)") (class "Default")
      (node (ref "IC2") (pin "24") (pinfunction "PC1(ADC1)_24") (pintype "bidirectional"))
    )
    (net (code "106") (name "unconnected-(IC2-PC2(ADC2)-Pad25)") (class "Default")
      (node (ref "IC2") (pin "25") (pinfunction "PC2(ADC2)_25") (pintype "bidirectional"))
    )
    (net (code "107") (name "unconnected-(IC2-PC3(ADC3)-Pad26)") (class "Default")
      (node (ref "IC2") (pin "26") (pinfunction "PC3(ADC3)_26") (pintype "bidirectional"))
    )
    (net (code "108") (name "unconnected-(IC2-PD2(INT0)-Pad32)") (class "Default")
      (node (ref "IC2") (pin "32") (pinfunction "PD2(INT0)_32") (pintype "bidirectional"))
    )
    (net (code "109") (name "unconnected-(IC2-PD3(INT1)-Pad1)") (class "Default")
      (node (ref "IC2") (pin "1") (pinfunction "PD3(INT1)_1") (pintype "bidirectional"))
    )
    (net (code "110") (name "unconnected-(IC2-PD4(XCK{slash}T0)-Pad2)") (class "Default")
      (node (ref "IC2") (pin "2") (pinfunction "PD4(XCK/T0)_2") (pintype "bidirectional"))
    )
    (net (code "111") (name "unconnected-(IC2-PD5(T1)-Pad9)") (class "Default")
      (node (ref "IC2") (pin "9") (pinfunction "PD5(T1)_9") (pintype "bidirectional"))
    )
    (net (code "112") (name "unconnected-(IC2-PD6(AIN0)-Pad10)") (class "Default")
      (node (ref "IC2") (pin "10") (pinfunction "PD6(AIN0)_10") (pintype "bidirectional"))
    )
    (net (code "113") (name "unconnected-(IC2-PD7(AIN1)-Pad11)") (class "Default")
      (node (ref "IC2") (pin "11") (pinfunction "PD7(AIN1)_11") (pintype "bidirectional"))
    )
    (net (code "114") (name "unconnected-(IC3-3V3OUT-Pad17)") (class "Default")
      (node (ref "IC3") (pin "17") (pinfunction "3V3OUT_17") (pintype "output"))
    )
    (net (code "115") (name "unconnected-(IC3-CTS-Pad11)") (class "Default")
      (node (ref "IC3") (pin "11") (pinfunction "CTS_11") (pintype "bidirectional"))
    )
    (net (code "116") (name "unconnected-(IC3-RTS-Pad3)") (class "Default")
      (node (ref "IC3") (pin "3") (pinfunction "RTS_3") (pintype "bidirectional"))
    )
    (net (code "117") (name "unconnected-(SW1-Pad3)") (class "Default")
      (node (ref "SW1") (pin "3") (pinfunction "3_3") (pintype "passive"))
    )
    (net (code "118") (name "unconnected-(U$1-1-PadP$1)") (class "Default")
      (node (ref "U$1") (pin "P$1") (pinfunction "1_P$1") (pintype "passive"))
    )
    (net (code "119") (name "unconnected-(U$1-2-PadP$2)") (class "Default")
      (node (ref "U$1") (pin "P$2") (pinfunction "2_P$2") (pintype "passive"))
    )
    (net (code "120") (name "unconnected-(U$1-3-PadP$3)") (class "Default")
      (node (ref "U$1") (pin "P$3") (pinfunction "3_P$3") (pintype "passive"))
    )
    (net (code "121") (name "unconnected-(U$1-4-PadP$4)") (class "Default")
      (node (ref "U$1") (pin "P$4") (pinfunction "4_P$4") (pintype "passive"))
    )
    (net (code "122") (name "unconnected-(U$1-5-PadP$5)") (class "Default")
      (node (ref "U$1") (pin "P$5") (pinfunction "5_P$5") (pintype "passive"))
    )
    (net (code "123") (name "unconnected-(U$1-8-PadP$8)") (class "Default")
      (node (ref "U$1") (pin "P$8") (pinfunction "8_P$8") (pintype "passive"))
    )
    (net (code "124") (name "unconnected-(U$1-9-PadP$9)") (class "Default")
      (node (ref "U$1") (pin "P$9") (pinfunction "9_P$9") (pintype "passive"))
    )
    (net (code "125") (name "unconnected-(U$1-10-PadP$10)") (class "Default")
      (node (ref "U$1") (pin "P$10") (pinfunction "10_P$10") (pintype "passive"))
    )
    (net (code "126") (name "unconnected-(U$1-11-PadP$11)") (class "Default")
      (node (ref "U$1") (pin "P$11") (pinfunction "11_P$11") (pintype "passive"))
    )
    (net (code "127") (name "unconnected-(U$1-12-PadP$12)") (class "Default")
      (node (ref "U$1") (pin "P$12") (pinfunction "12_P$12") (pintype "passive"))
    )
    (net (code "128") (name "unconnected-(U$1-13-PadP$13)") (class "Default")
      (node (ref "U$1") (pin "P$13") (pinfunction "13_P$13") (pintype "passive"))
    )
    (net (code "129") (name "unconnected-(U$1-14-PadP$14)") (class "Default")
      (node (ref "U$1") (pin "P$14") (pinfunction "14_P$14") (pintype "passive"))
    )
    (net (code "130") (name "unconnected-(U$1-15-PadP$15)") (class "Default")
      (node (ref "U$1") (pin "P$15") (pinfunction "15_P$15") (pintype "passive"))
    )
    (net (code "131") (name "unconnected-(U$1-16-PadP$16)") (class "Default")
      (node (ref "U$1") (pin "P$16") (pinfunction "16_P$16") (pintype "passive"))
    )
    (net (code "132") (name "unconnected-(U$1-19-PadP$19)") (class "Default")
      (node (ref "U$1") (pin "P$19") (pinfunction "19_P$19") (pintype "passive"))
    )
    (net (code "133") (name "unconnected-(U$1-20-PadP$20)") (class "Default")
      (node (ref "U$1") (pin "P$20") (pinfunction "20_P$20") (pintype "passive"))
    )
    (net (code "134") (name "unconnected-(USB1-Pad2)") (class "Default")
      (node (ref "USB1") (pin "2") (pinfunction "2_2") (pintype "input"))
    )
  )
)
